# CAN_Transceiver.net
KiCad netlist of a schematic drawn in Altium Designer
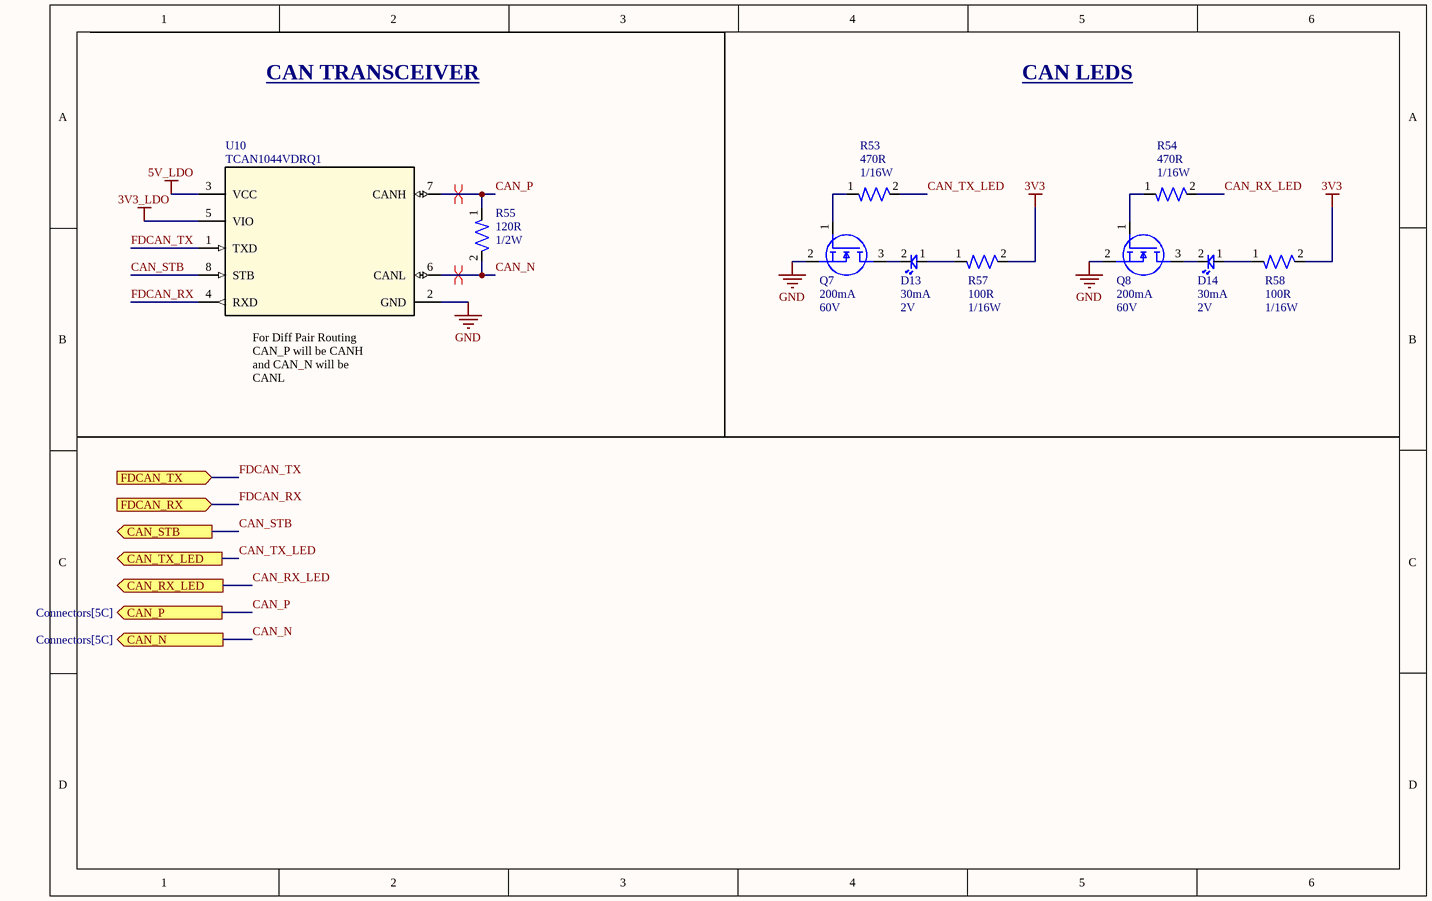
[diagram p0: CAN_Transceiver.SchDoc]

(export (version "E")
  (design (tool "Eeschema 10.0.6"))
  (components
    (comp (ref "D13")
      (value "BL-HKC36G-AV-TRB")
      (footprint "LED-0603")
      (description "LED YELLOW CLEAR 0603 SMD")
      (fields (field (name "FORWARD CURRENT") "30mA") (field (name "FORWARD VOLTAGE") "2V"))
      (libsource (lib "JLC_25") (part "LED-0001"))
    )
    (comp (ref "D14")
      (value "BL-HKC36G-AV-TRB")
      (footprint "LED-0603")
      (description "LED YELLOW CLEAR 0603 SMD")
      (fields (field (name "FORWARD CURRENT") "30mA") (field (name "FORWARD VOLTAGE") "2V"))
      (libsource (lib "JLC_25") (part "LED-0001"))
    )
    (comp (ref "Q7")
      (value "T2N7002AK,LM")
      (footprint "IC-SOT23-3")
      (description "MOSFET N-CH 60V 200MA SOT23")
      (fields (field (name "CONTINUOUS CURRENT") "200mA") (field (name "VOLTAGE") "60V"))
      (libsource (lib "JLC_25") (part "NMOS-200MA-0001"))
    )
    (comp (ref "Q8")
      (value "T2N7002AK,LM")
      (footprint "IC-SOT23-3")
      (description "MOSFET N-CH 60V 200MA SOT23")
      (fields (field (name "CONTINUOUS CURRENT") "200mA") (field (name "VOLTAGE") "60V"))
      (libsource (lib "JLC_25") (part "NMOS-200MA-0001"))
    )
    (comp (ref "R53")
      (value "RC0402FR-07470RL")
      (footprint "RES-0402")
      (description "RES 470 OHM 1% 1/16W 0402")
      (fields
        (field (name "TOLERANCE") "1%")
        (field (name "POWER") "1/16W")
        (field (name "RESISTANCE") "470R")
      )
      (libsource (lib "JLC_25") (part "RES-470-0001"))
    )
    (comp (ref "R54")
      (value "RC0402FR-07470RL")
      (footprint "RES-0402")
      (description "RES 470 OHM 1% 1/16W 0402")
      (fields
        (field (name "TOLERANCE") "1%")
        (field (name "POWER") "1/16W")
        (field (name "RESISTANCE") "470R")
      )
      (libsource (lib "JLC_25") (part "RES-470-0001"))
    )
    (comp (ref "R55")
      (value "RC1210FR-07120RL")
      (footprint "RES-1210")
      (description "RES 120 OHM 1% 1/2W 1210")
      (fields
        (field (name "TOLERANCE") "1%")
        (field (name "POWER") "1/2W")
        (field (name "RESISTANCE") "120R")
      )
      (libsource (lib "JLC_25") (part "RES-120-0001"))
    )
    (comp (ref "R57")
      (value "RC0402FR-07100RL")
      (footprint "RES-0402")
      (description "RES 100 OHM 1% 1/16W 0402")
      (fields
        (field (name "TOLERANCE") "1%")
        (field (name "POWER") "1/16W")
        (field (name "RESISTANCE") "100R")
      )
      (libsource (lib "JLC_25") (part "RES-100-0001"))
    )
    (comp (ref "R58")
      (value "RC0402FR-07100RL")
      (footprint "RES-0402")
      (description "RES 100 OHM 1% 1/16W 0402")
      (fields
        (field (name "TOLERANCE") "1%")
        (field (name "POWER") "1/16W")
        (field (name "RESISTANCE") "100R")
      )
      (libsource (lib "JLC_25") (part "RES-100-0001"))
    )
    (comp (ref "U10")
      (value "TCAN1044VDRQ1")
      (footprint "IC-8SOIC")
      (description "IC TRANSCEIVER 1/1 8SOIC")
      (libsource (lib "JLC_25") (part "IC-CAN-0001"))
    )
  )
  (nets
    (net (code "1") (name "/CAN_N") (class "Default")
      (node (ref "R55") (pin "2") (pinfunction "2_2") (pintype "passive"))
      (node (ref "U10") (pin "6") (pinfunction "CANL_6") (pintype "bidirectional"))
    )
    (net (code "2") (name "/CAN_P") (class "Default")
      (node (ref "R55") (pin "1") (pinfunction "1_1") (pintype "passive"))
      (node (ref "U10") (pin "7") (pinfunction "CANH_7") (pintype "bidirectional"))
    )
    (net (code "3") (name "/CAN_RX_LED") (class "Default")
      (node (ref "R54") (pin "2") (pinfunction "2_2") (pintype "passive"))
    )
    (net (code "4") (name "/CAN_STB") (class "Default")
      (node (ref "U10") (pin "8") (pinfunction "STB_8") (pintype "input"))
    )
    (net (code "5") (name "/CAN_TX_LED") (class "Default")
      (node (ref "R53") (pin "2") (pinfunction "2_2") (pintype "passive"))
    )
    (net (code "6") (name "/FDCAN_RX") (class "Default")
      (node (ref "U10") (pin "4") (pinfunction "RXD_4") (pintype "output"))
    )
    (net (code "7") (name "/FDCAN_TX") (class "Default")
      (node (ref "U10") (pin "1") (pinfunction "TXD_1") (pintype "input"))
    )
    (net (code "8") (name "3V3") (class "Default")
      (node (ref "R57") (pin "2") (pinfunction "2_2") (pintype "passive"))
      (node (ref "R58") (pin "2") (pinfunction "2_2") (pintype "passive"))
    )
    (net (code "9") (name "3V3_LDO") (class "Default")
      (node (ref "U10") (pin "5") (pinfunction "VIO_5") (pintype "power_in"))
    )
    (net (code "10") (name "5V_LDO") (class "Default")
      (node (ref "U10") (pin "3") (pinfunction "VCC_3") (pintype "power_in"))
    )
    (net (code "11") (name "GND") (class "Default")
      (node (ref "Q7") (pin "2") (pinfunction "S_2") (pintype "passive"))
      (node (ref "Q8") (pin "2") (pinfunction "S_2") (pintype "passive"))
      (node (ref "U10") (pin "2") (pinfunction "GND_2") (pintype "power_in"))
    )
    (net (code "12") (name "Net-(D13-Pad1)") (class "Default")
      (node (ref "D13") (pin "1") (pinfunction "1_1") (pintype "passive"))
      (node (ref "R57") (pin "1") (pinfunction "1_1") (pintype "passive"))
    )
    (net (code "13") (name "Net-(D14-Pad1)") (class "Default")
      (node (ref "D14") (pin "1") (pinfunction "1_1") (pintype "passive"))
      (node (ref "R58") (pin "1") (pinfunction "1_1") (pintype "passive"))
    )
    (net (code "14") (name "Net-(Q7-D)") (class "Default")
      (node (ref "D13") (pin "2") (pinfunction "2_2") (pintype "passive"))
      (node (ref "Q7") (pin "3") (pinfunction "D_3") (pintype "passive"))
    )
    (net (code "15") (name "Net-(Q7-G)") (class "Default")
      (node (ref "Q7") (pin "1") (pinfunction "G_1") (pintype "passive"))
      (node (ref "R53") (pin "1") (pinfunction "1_1") (pintype "passive"))
    )
    (net (code "16") (name "Net-(Q8-D)") (class "Default")
      (node (ref "D14") (pin "2") (pinfunction "2_2") (pintype "passive"))
      (node (ref "Q8") (pin "3") (pinfunction "D_3") (pintype "passive"))
    )
    (net (code "17") (name "Net-(Q8-G)") (class "Default")
      (node (ref "Q8") (pin "1") (pinfunction "G_1") (pintype "passive"))
      (node (ref "R54") (pin "1") (pinfunction "1_1") (pintype "passive"))
    )
  )
)
